# arduino_nano.net
KiCad netlist of a schematic drawn in EAGLE
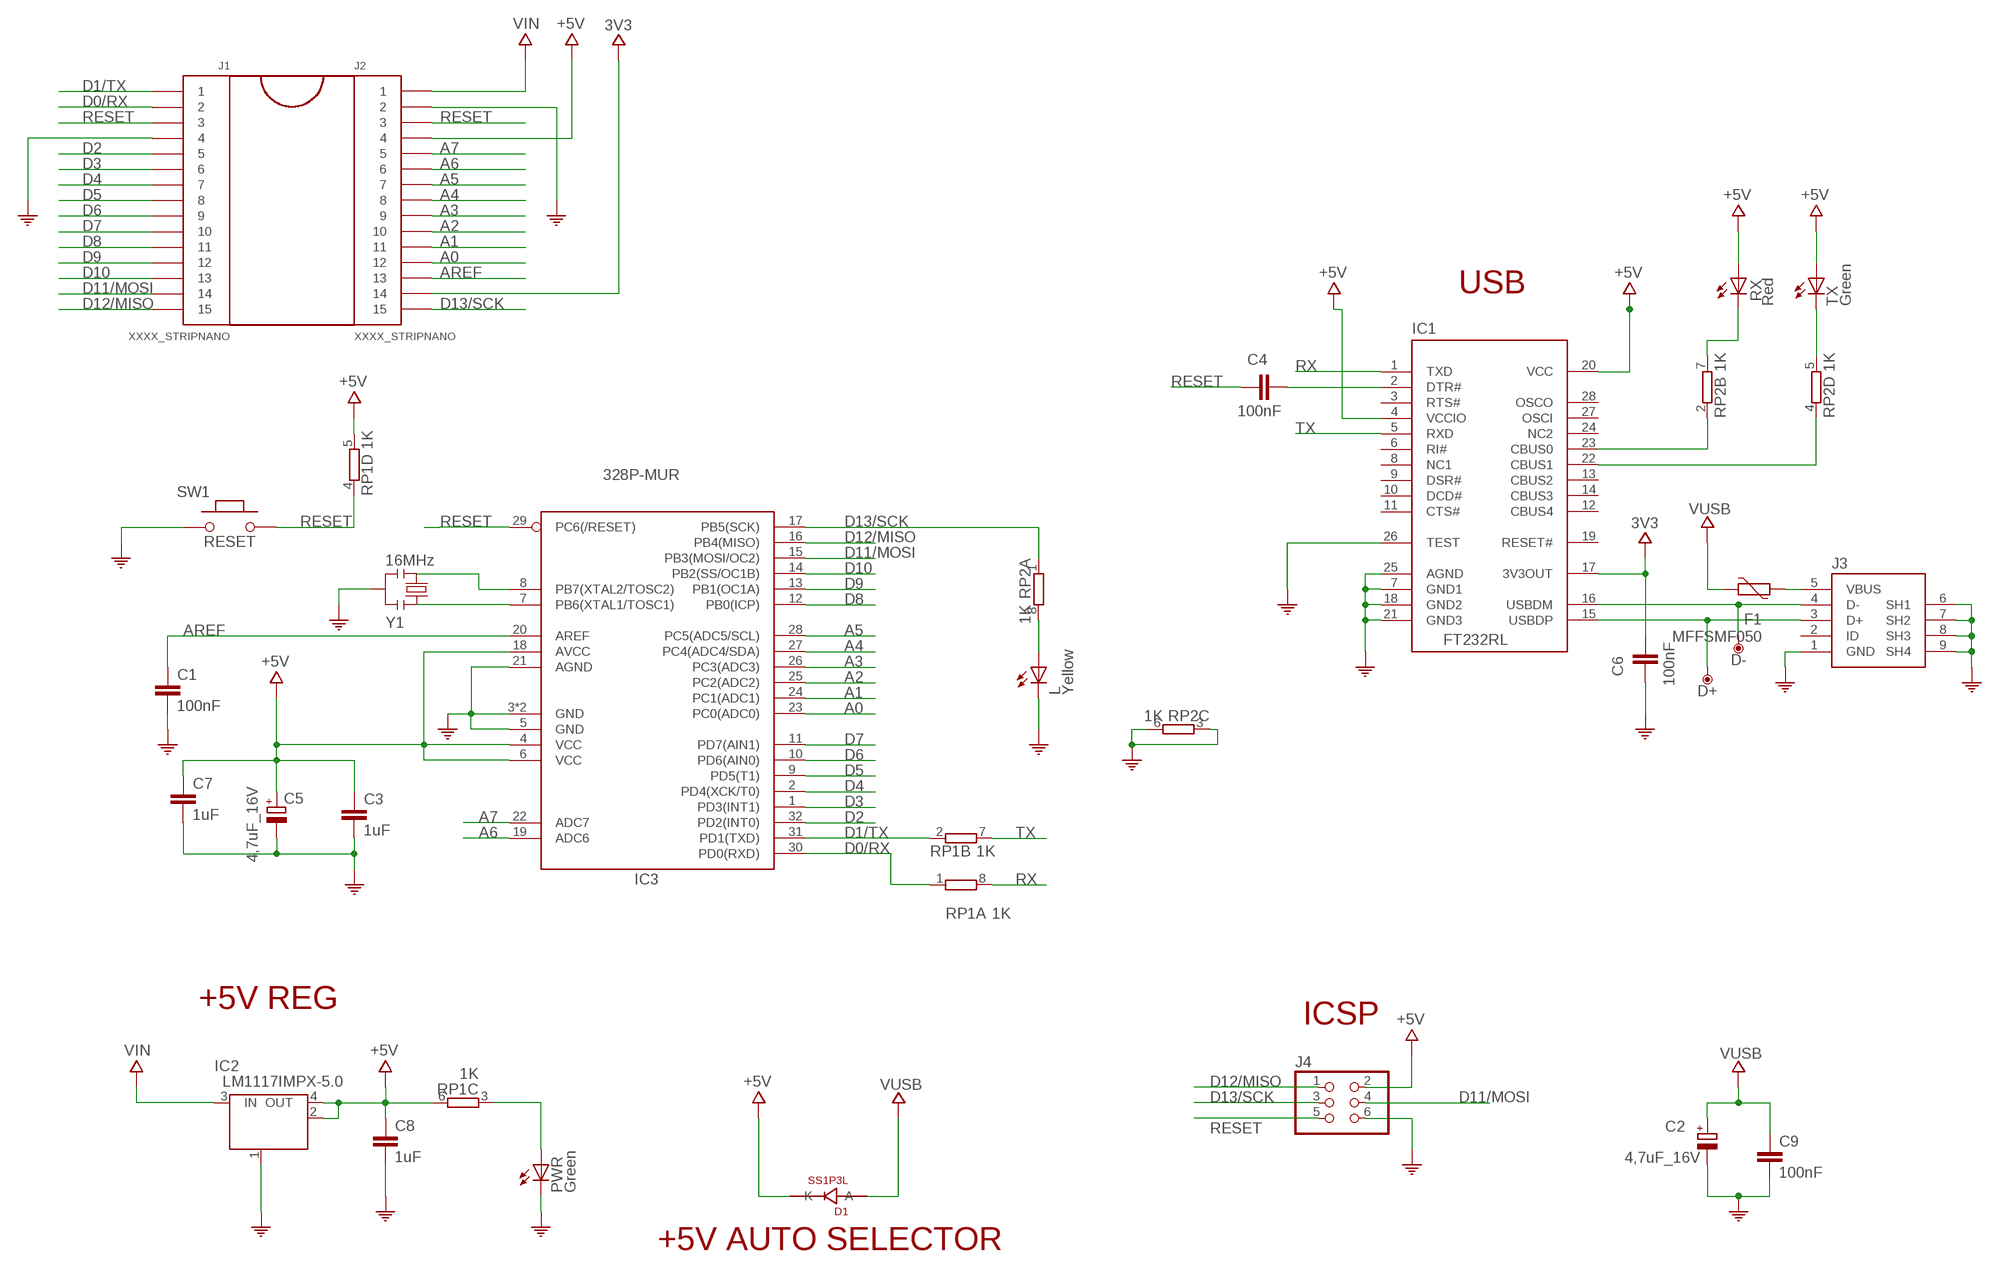
[diagram p0: schematic, sheet 1]

(export (version "E")
  (design (tool "Eeschema 10.0.6"))
  (components
    (comp (ref "C1")
      (value "100nF")
      (footprint "eagle-import:C0603-ROUND")
      (fields (field (name "PART_NUMBER") "cl10b104kbnc"))
      (libsource (lib "eagle-import") (part "0015_100NF_0603"))
    )
    (comp (ref "C2")
      (value "4,7uF_16V")
      (footprint "eagle-import:TAN-A")
      (fields (field (name "PART_NUMBER") "TAJA475MO16RNJ"))
      (libsource (lib "eagle-import") (part "0833_TAJA475MO16RNJ"))
    )
    (comp (ref "C3")
      (value "1uF")
      (footprint "eagle-import:C0603-ROUND")
      (fields (field (name "PART_NUMBER") "1uF_0603/GRM188R61E105KA12D"))
      (libsource (lib "eagle-import") (part "0006_1UF_0603/GRM188R61E105KA12D"))
    )
    (comp (ref "C4")
      (value "100nF")
      (footprint "eagle-import:C0603-ROUND")
      (fields (field (name "PART_NUMBER") "cl10b104kbnc"))
      (libsource (lib "eagle-import") (part "0015_100NF_0603"))
    )
    (comp (ref "C5")
      (value "4,7uF_16V")
      (footprint "eagle-import:TAN-A")
      (fields (field (name "PART_NUMBER") "TAJA475MO16RNJ"))
      (libsource (lib "eagle-import") (part "0833_TAJA475MO16RNJ"))
    )
    (comp (ref "C6")
      (value "100nF")
      (footprint "eagle-import:C0603-ROUND")
      (fields (field (name "PART_NUMBER") "cl10b104kbnc"))
      (libsource (lib "eagle-import") (part "0015_100NF_0603"))
    )
    (comp (ref "C7")
      (value "1uF")
      (footprint "eagle-import:C0603-ROUND")
      (fields (field (name "PART_NUMBER") "1uF_0603/GRM188R61E105KA12D"))
      (libsource (lib "eagle-import") (part "0006_1UF_0603/GRM188R61E105KA12D"))
    )
    (comp (ref "C8")
      (value "1uF")
      (footprint "eagle-import:C0603-ROUND")
      (fields (field (name "PART_NUMBER") "1uF_0603/GRM188R61E105KA12D"))
      (libsource (lib "eagle-import") (part "0006_1UF_0603/GRM188R61E105KA12D"))
    )
    (comp (ref "C9")
      (value "100nF")
      (footprint "eagle-import:C0603-ROUND")
      (fields (field (name "PART_NUMBER") "cl10b104kbnc"))
      (libsource (lib "eagle-import") (part "0015_100NF_0603"))
    )
    (comp (ref "D+")
      (value "DNP")
      (footprint "eagle-import:TP-1.00MM")
      (libsource (lib "eagle-import") (part "TPTP-1.00MM"))
    )
    (comp (ref "D-")
      (value "DNP")
      (footprint "eagle-import:TP-1.00MM")
      (libsource (lib "eagle-import") (part "TPTP-1.00MM"))
    )
    (comp (ref "D1")
      (value "SS1P3L")
      (footprint "eagle-import:DO220AAL")
      (fields (field (name "PART_NUMBER") "SS1P3L-M3/84A"))
      (libsource (lib "eagle-import") (part "0025_SS1P3L-M3/84A"))
    )
    (comp (ref "F1")
      (value "MFFSMF050")
      (footprint "eagle-import:0603-1608X90N")
      (fields (field (name "MANUFACTURER") "Bourns Inc "))
      (libsource (lib "eagle-import") (part "PTC"))
    )
    (comp (ref "IC1")
      (value "FT232RL")
      (footprint "eagle-import:SSOP28")
      (libsource (lib "eagle-import") (part "0226_FT232RL"))
    )
    (comp (ref "IC2")
      (value "LM1117IMPX-5.0")
      (footprint "eagle-import:LINEAR_SOT223")
      (libsource (lib "eagle-import") (part "0022_LM1117IMPX-5.0"))
    )
    (comp (ref "IC3")
      (value "328P-MUR")
      (footprint "eagle-import:VQFN32")
      (fields (field (name "MANUFACTURER") "ATMEL"))
      (libsource (lib "eagle-import") (part "ATMEGA328P-32MUR"))
    )
    (comp (ref "J1")
      (value "XXXX_STRIPNANO")
      (footprint "eagle-import:HEAD15-NOSS")
      (libsource (lib "eagle-import") (part "XXXX_STRIPNANO"))
    )
    (comp (ref "J2")
      (value "XXXX_STRIPNANO")
      (footprint "eagle-import:HEAD15-NOSS")
      (libsource (lib "eagle-import") (part "XXXX_STRIPNANO"))
    )
    (comp (ref "J3")
      (value "0219_14850")
      (footprint "eagle-import:USB-MINI-B_2")
      (fields (field (name "PART_NUMBER") "14850"))
      (libsource (lib "eagle-import") (part "0219_14850"))
    )
    (comp (ref "J4")
      (value "0114_PH254-203DF118A00V")
      (footprint "eagle-import:2X03")
      (fields (field (name "PART_NUMBER") "PH254-203DF118A00V"))
      (libsource (lib "eagle-import") (part "0114_PH254-203DF118A00V"))
    )
    (comp (ref "L")
      (value "Yellow")
      (footprint "eagle-import:CHIPLED_0805")
      (fields (field (name "PART_NUMBER") "KPT-2012YC"))
      (libsource (lib "eagle-import") (part "0044_KPT-2012YC"))
    )
    (comp (ref "PWR")
      (value "Green")
      (footprint "eagle-import:CHIPLED_0805")
      (fields (field (name "PART_NUMBER") "KPT-2012SGC"))
      (libsource (lib "eagle-import") (part "0043_KPT-2012SGC"))
    )
    (comp (ref "RP1")
      (value "1K")
      (footprint "eagle-import:CAY16")
      (fields (field (name "PART_NUMBER") "064R_1K_/_CAY16-102J4LF"))
      (libsource (lib "eagle-import") (part "0005_064R_1K_/_CAY16-102J4LF"))
    )
    (comp (ref "RP2")
      (value "1K")
      (footprint "eagle-import:CAY16")
      (fields (field (name "PART_NUMBER") "064R_1K_/_CAY16-102J4LF"))
      (libsource (lib "eagle-import") (part "0005_064R_1K_/_CAY16-102J4LF"))
    )
    (comp (ref "RX")
      (value "Red")
      (footprint "eagle-import:CHIPLED_0805")
      (fields (field (name "PART_NUMBER") "KTP-2012SURCK"))
      (libsource (lib "eagle-import") (part "0181_KTP-2012SURCK"))
    )
    (comp (ref "SW1")
      (value "RESET")
      (footprint "eagle-import:SMD_157SW")
      (fields (field (name "PART_NUMBER") "IT-1185AP1C-160G-G_T&R"))
      (libsource (lib "eagle-import") (part "0173_IT-1185AP1C-160G-G_T&R"))
    )
    (comp (ref "TX")
      (value "Green")
      (footprint "eagle-import:CHIPLED_0805")
      (fields (field (name "PART_NUMBER") "KPT-2012SGC"))
      (libsource (lib "eagle-import") (part "0043_KPT-2012SGC"))
    )
    (comp (ref "Y1")
      (value "16MHz")
      (footprint "eagle-import:RESONATOR")
      (fields (field (name "PART_NUMBER") "CSTCE16M0V53-R0"))
      (libsource (lib "eagle-import") (part "0011_CSTCE16M0V53-R0"))
    )
  )
  (nets
    (net (code "1") (name "+5V") (class "Default")
      (node (ref "C3") (pin "1") (pinfunction "1_1") (pintype "passive"))
      (node (ref "C5") (pin "1") (pinfunction "+_1") (pintype "passive"))
      (node (ref "C7") (pin "1") (pinfunction "1_1") (pintype "passive"))
      (node (ref "C8") (pin "1") (pinfunction "1_1") (pintype "passive"))
      (node (ref "D1") (pin "P$1") (pinfunction "K_P$1") (pintype "bidirectional"))
      (node (ref "IC1") (pin "20") (pinfunction "VCC_20") (pintype "power_in"))
      (node (ref "IC1") (pin "4") (pinfunction "VCCIO_4") (pintype "power_in"))
      (node (ref "IC2") (pin "2") (pinfunction "OUT_2") (pintype "passive"))
      (node (ref "IC2") (pin "4") (pinfunction "OUT_4") (pintype "passive"))
      (node (ref "IC3") (pin "18") (pinfunction "AVCC_18") (pintype "bidirectional"))
      (node (ref "IC3") (pin "4") (pinfunction "VCC_4") (pintype "bidirectional"))
      (node (ref "IC3") (pin "6") (pinfunction "VCC_6") (pintype "bidirectional"))
      (node (ref "J2") (pin "4") (pinfunction "4_4") (pintype "passive"))
      (node (ref "J4") (pin "2") (pinfunction "2_2") (pintype "passive"))
      (node (ref "RP1") (pin "5") (pinfunction "2_5") (pintype "passive"))
      (node (ref "RP1") (pin "6") (pinfunction "2_6") (pintype "passive"))
      (node (ref "RX") (pin "A") (pinfunction "A_A") (pintype "passive"))
      (node (ref "TX") (pin "A") (pinfunction "A_A") (pintype "passive"))
    )
    (net (code "2") (name "/A0") (class "Default")
      (node (ref "IC3") (pin "23") (pinfunction "PC0(ADC0)_23") (pintype "bidirectional"))
      (node (ref "J2") (pin "12") (pinfunction "12_12") (pintype "passive"))
    )
    (net (code "3") (name "/A1") (class "Default")
      (node (ref "IC3") (pin "24") (pinfunction "PC1(ADC1)_24") (pintype "bidirectional"))
      (node (ref "J2") (pin "11") (pinfunction "11_11") (pintype "passive"))
    )
    (net (code "4") (name "/A2") (class "Default")
      (node (ref "IC3") (pin "25") (pinfunction "PC2(ADC2)_25") (pintype "bidirectional"))
      (node (ref "J2") (pin "10") (pinfunction "10_10") (pintype "passive"))
    )
    (net (code "5") (name "/A3") (class "Default")
      (node (ref "IC3") (pin "26") (pinfunction "PC3(ADC3)_26") (pintype "bidirectional"))
      (node (ref "J2") (pin "9") (pinfunction "9_9") (pintype "passive"))
    )
    (net (code "6") (name "/A4") (class "Default")
      (node (ref "IC3") (pin "27") (pinfunction "PC4(ADC4/SDA)_27") (pintype "bidirectional"))
      (node (ref "J2") (pin "8") (pinfunction "8_8") (pintype "passive"))
    )
    (net (code "7") (name "/A5") (class "Default")
      (node (ref "IC3") (pin "28") (pinfunction "PC5(ADC5/SCL)_28") (pintype "bidirectional"))
      (node (ref "J2") (pin "7") (pinfunction "7_7") (pintype "passive"))
    )
    (net (code "8") (name "/A6") (class "Default")
      (node (ref "IC3") (pin "19") (pinfunction "ADC6_19") (pintype "bidirectional"))
      (node (ref "J2") (pin "6") (pinfunction "6_6") (pintype "passive"))
    )
    (net (code "9") (name "/A7") (class "Default")
      (node (ref "IC3") (pin "22") (pinfunction "ADC7_22") (pintype "bidirectional"))
      (node (ref "J2") (pin "5") (pinfunction "5_5") (pintype "passive"))
    )
    (net (code "10") (name "/AREF") (class "Default")
      (node (ref "C1") (pin "1") (pinfunction "1_1") (pintype "passive"))
      (node (ref "IC3") (pin "20") (pinfunction "AREF_20") (pintype "bidirectional"))
      (node (ref "J2") (pin "13") (pinfunction "13_13") (pintype "passive"))
    )
    (net (code "11") (name "/D0{slash}RX") (class "Default")
      (node (ref "IC3") (pin "30") (pinfunction "PD0(RXD)_30") (pintype "bidirectional"))
      (node (ref "J1") (pin "2") (pinfunction "2_2") (pintype "passive"))
      (node (ref "RP1") (pin "1") (pinfunction "1_1") (pintype "passive"))
    )
    (net (code "12") (name "/D1{slash}TX") (class "Default")
      (node (ref "IC3") (pin "31") (pinfunction "PD1(TXD)_31") (pintype "bidirectional"))
      (node (ref "J1") (pin "1") (pinfunction "1_1") (pintype "passive"))
      (node (ref "RP1") (pin "2") (pinfunction "1_2") (pintype "passive"))
    )
    (net (code "13") (name "/D2") (class "Default")
      (node (ref "IC3") (pin "32") (pinfunction "PD2(INT0)_32") (pintype "bidirectional"))
      (node (ref "J1") (pin "5") (pinfunction "5_5") (pintype "passive"))
    )
    (net (code "14") (name "/D3") (class "Default")
      (node (ref "IC3") (pin "1") (pinfunction "PD3(INT1)_1") (pintype "bidirectional"))
      (node (ref "J1") (pin "6") (pinfunction "6_6") (pintype "passive"))
    )
    (net (code "15") (name "/D4") (class "Default")
      (node (ref "IC3") (pin "2") (pinfunction "PD4(XCK/T0)_2") (pintype "bidirectional"))
      (node (ref "J1") (pin "7") (pinfunction "7_7") (pintype "passive"))
    )
    (net (code "16") (name "/D5") (class "Default")
      (node (ref "IC3") (pin "9") (pinfunction "PD5(T1)_9") (pintype "bidirectional"))
      (node (ref "J1") (pin "8") (pinfunction "8_8") (pintype "passive"))
    )
    (net (code "17") (name "/D6") (class "Default")
      (node (ref "IC3") (pin "10") (pinfunction "PD6(AIN0)_10") (pintype "bidirectional"))
      (node (ref "J1") (pin "9") (pinfunction "9_9") (pintype "passive"))
    )
    (net (code "18") (name "/D7") (class "Default")
      (node (ref "IC3") (pin "11") (pinfunction "PD7(AIN1)_11") (pintype "bidirectional"))
      (node (ref "J1") (pin "10") (pinfunction "10_10") (pintype "passive"))
    )
    (net (code "19") (name "/D8") (class "Default")
      (node (ref "IC3") (pin "12") (pinfunction "PB0(ICP)_12") (pintype "bidirectional"))
      (node (ref "J1") (pin "11") (pinfunction "11_11") (pintype "passive"))
    )
    (net (code "20") (name "/D9") (class "Default")
      (node (ref "IC3") (pin "13") (pinfunction "PB1(OC1A)_13") (pintype "bidirectional"))
      (node (ref "J1") (pin "12") (pinfunction "12_12") (pintype "passive"))
    )
    (net (code "21") (name "/D10") (class "Default")
      (node (ref "IC3") (pin "14") (pinfunction "PB2(SS/OC1B)_14") (pintype "bidirectional"))
      (node (ref "J1") (pin "13") (pinfunction "13_13") (pintype "passive"))
    )
    (net (code "22") (name "/D11{slash}MOSI") (class "Default")
      (node (ref "IC3") (pin "15") (pinfunction "PB3(MOSI/OC2)_15") (pintype "bidirectional"))
      (node (ref "J1") (pin "14") (pinfunction "14_14") (pintype "passive"))
      (node (ref "J4") (pin "4") (pinfunction "4_4") (pintype "passive"))
    )
    (net (code "23") (name "/D12{slash}MISO") (class "Default")
      (node (ref "IC3") (pin "16") (pinfunction "PB4(MISO)_16") (pintype "bidirectional"))
      (node (ref "J1") (pin "15") (pinfunction "15_15") (pintype "passive"))
      (node (ref "J4") (pin "1") (pinfunction "1_1") (pintype "passive"))
    )
    (net (code "24") (name "/D13{slash}SCK") (class "Default")
      (node (ref "IC3") (pin "17") (pinfunction "PB5(SCK)_17") (pintype "bidirectional"))
      (node (ref "J2") (pin "15") (pinfunction "15_15") (pintype "passive"))
      (node (ref "J4") (pin "3") (pinfunction "3_3") (pintype "passive"))
      (node (ref "RP2") (pin "1") (pinfunction "1_1") (pintype "passive"))
    )
    (net (code "25") (name "/RESET") (class "Default")
      (node (ref "C4") (pin "1") (pinfunction "1_1") (pintype "passive"))
      (node (ref "IC3") (pin "29") (pinfunction "PC6(/RESET)_29") (pintype "bidirectional"))
      (node (ref "J1") (pin "3") (pinfunction "3_3") (pintype "passive"))
      (node (ref "J2") (pin "3") (pinfunction "3_3") (pintype "passive"))
      (node (ref "J4") (pin "5") (pinfunction "5_5") (pintype "passive"))
      (node (ref "RP1") (pin "4") (pinfunction "1_4") (pintype "passive"))
      (node (ref "SW1") (pin "2") (pinfunction "2_2") (pintype "passive"))
    )
    (net (code "26") (name "/RX") (class "Default")
      (node (ref "IC1") (pin "1") (pinfunction "TXD_1") (pintype "output"))
      (node (ref "RP1") (pin "8") (pinfunction "2_8") (pintype "passive"))
      (node (ref "RP2") (pin "7") (pinfunction "2_7") (pintype "passive"))
      (node (ref "RX") (pin "C") (pinfunction "C_C") (pintype "passive"))
    )
    (net (code "27") (name "/TX") (class "Default")
      (node (ref "IC1") (pin "5") (pinfunction "RXD_5") (pintype "input"))
      (node (ref "RP1") (pin "7") (pinfunction "2_7") (pintype "passive"))
    )
    (net (code "28") (name "3V3") (class "Default")
      (node (ref "C6") (pin "2") (pinfunction "2_2") (pintype "passive"))
      (node (ref "IC1") (pin "17") (pinfunction "3V3OUT_17") (pintype "power_in"))
      (node (ref "J2") (pin "14") (pinfunction "14_14") (pintype "passive"))
    )
    (net (code "29") (name "COM") (class "Default")
      (node (ref "C1") (pin "2") (pinfunction "2_2") (pintype "passive"))
      (node (ref "C2") (pin "2") (pinfunction "-_2") (pintype "passive"))
      (node (ref "C3") (pin "2") (pinfunction "2_2") (pintype "passive"))
      (node (ref "C5") (pin "2") (pinfunction "-_2") (pintype "passive"))
      (node (ref "C6") (pin "1") (pinfunction "1_1") (pintype "passive"))
      (node (ref "C7") (pin "2") (pinfunction "2_2") (pintype "passive"))
      (node (ref "C8") (pin "2") (pinfunction "2_2") (pintype "passive"))
      (node (ref "C9") (pin "2") (pinfunction "2_2") (pintype "passive"))
      (node (ref "IC1") (pin "18") (pinfunction "GND2_18") (pintype "power_in"))
      (node (ref "IC1") (pin "21") (pinfunction "GND3_21") (pintype "power_in"))
      (node (ref "IC1") (pin "25") (pinfunction "AGND_25") (pintype "power_in"))
      (node (ref "IC1") (pin "26") (pinfunction "TEST_26") (pintype "bidirectional"))
      (node (ref "IC1") (pin "7") (pinfunction "GND1_7") (pintype "power_in"))
      (node (ref "IC2") (pin "1") (pinfunction "GND/ADJ_1") (pintype "input"))
      (node (ref "IC3") (pin "21") (pinfunction "AGND_21") (pintype "bidirectional"))
      (node (ref "IC3") (pin "3") (pinfunction "GND_3") (pintype "bidirectional"))
      (node (ref "IC3") (pin "33") (pinfunction "GND_33") (pintype "bidirectional"))
      (node (ref "IC3") (pin "5") (pinfunction "GND_5") (pintype "bidirectional"))
      (node (ref "J1") (pin "4") (pinfunction "4_4") (pintype "passive"))
      (node (ref "J2") (pin "2") (pinfunction "2_2") (pintype "passive"))
      (node (ref "J3") (pin "1") (pinfunction "GND_1") (pintype "passive"))
      (node (ref "J3") (pin "6") (pinfunction "SH1_6") (pintype "passive"))
      (node (ref "J3") (pin "7") (pinfunction "SH2_7") (pintype "passive"))
      (node (ref "J3") (pin "8") (pinfunction "SH3_8") (pintype "passive"))
      (node (ref "J3") (pin "9") (pinfunction "SH4_9") (pintype "passive"))
      (node (ref "J4") (pin "6") (pinfunction "6_6") (pintype "passive"))
      (node (ref "L") (pin "C") (pinfunction "C_C") (pintype "passive"))
      (node (ref "PWR") (pin "C") (pinfunction "C_C") (pintype "passive"))
      (node (ref "RP2") (pin "3") (pinfunction "1_3") (pintype "passive"))
      (node (ref "RP2") (pin "6") (pinfunction "2_6") (pintype "passive"))
      (node (ref "SW1") (pin "1") (pinfunction "1_1") (pintype "passive"))
      (node (ref "Y1") (pin "2") (pinfunction "2_2") (pintype "passive"))
    )
    (net (code "30") (name "Net-(D+-P$1)") (class "Default")
      (node (ref "D+") (pin "X") (pinfunction "P$1_X") (pintype "passive"))
      (node (ref "IC1") (pin "15") (pinfunction "USBDP_15") (pintype "bidirectional"))
      (node (ref "J3") (pin "3") (pinfunction "D+_3") (pintype "bidirectional"))
    )
    (net (code "31") (name "Net-(D--P$1)") (class "Default")
      (node (ref "D-") (pin "X") (pinfunction "P$1_X") (pintype "passive"))
      (node (ref "IC1") (pin "16") (pinfunction "USBDM_16") (pintype "bidirectional"))
      (node (ref "J3") (pin "4") (pinfunction "D-_4") (pintype "bidirectional"))
    )
    (net (code "32") (name "Net-(IC1-CBUS0)") (class "Default")
      (node (ref "IC1") (pin "23") (pinfunction "CBUS0_23") (pintype "bidirectional"))
      (node (ref "RP2") (pin "2") (pinfunction "1_2") (pintype "passive"))
    )
    (net (code "33") (name "Net-(IC1-CBUS1)") (class "Default")
      (node (ref "IC1") (pin "22") (pinfunction "CBUS1_22") (pintype "bidirectional"))
      (node (ref "RP2") (pin "4") (pinfunction "1_4") (pintype "passive"))
    )
    (net (code "34") (name "Net-(IC1-DTR#)") (class "Default")
      (node (ref "C4") (pin "2") (pinfunction "2_2") (pintype "passive"))
      (node (ref "IC1") (pin "2") (pinfunction "DTR#_2") (pintype "output"))
    )
    (net (code "35") (name "Net-(IC3-PB6(XTAL1{slash}TOSC1))") (class "Default")
      (node (ref "IC3") (pin "7") (pinfunction "PB6(XTAL1/TOSC1)_7") (pintype "bidirectional"))
      (node (ref "Y1") (pin "1") (pinfunction "1_1") (pintype "passive"))
    )
    (net (code "36") (name "Net-(IC3-PB7(XTAL2{slash}TOSC2))") (class "Default")
      (node (ref "IC3") (pin "8") (pinfunction "PB7(XTAL2/TOSC2)_8") (pintype "bidirectional"))
      (node (ref "Y1") (pin "3") (pinfunction "3_3") (pintype "passive"))
    )
    (net (code "37") (name "Net-(J3-VBUS)") (class "Default")
      (node (ref "F1") (pin "2") (pinfunction "2_2") (pintype "passive"))
      (node (ref "J3") (pin "5") (pinfunction "VBUS_5") (pintype "power_in"))
    )
    (net (code "38") (name "Net-(RP1C-1)") (class "Default")
      (node (ref "PWR") (pin "A") (pinfunction "A_A") (pintype "passive"))
      (node (ref "RP1") (pin "3") (pinfunction "1_3") (pintype "passive"))
    )
    (net (code "39") (name "Net-(RP2A-2)") (class "Default")
      (node (ref "L") (pin "A") (pinfunction "A_A") (pintype "passive"))
      (node (ref "RP2") (pin "8") (pinfunction "2_8") (pintype "passive"))
    )
    (net (code "40") (name "Net-(RP2D-2)") (class "Default")
      (node (ref "RP2") (pin "5") (pinfunction "2_5") (pintype "passive"))
      (node (ref "TX") (pin "C") (pinfunction "C_C") (pintype "passive"))
    )
    (net (code "41") (name "VIN") (class "Default")
      (node (ref "IC2") (pin "3") (pinfunction "IN_3") (pintype "input"))
      (node (ref "J2") (pin "1") (pinfunction "1_1") (pintype "passive"))
    )
    (net (code "42") (name "VUSB") (class "Default")
      (node (ref "C2") (pin "1") (pinfunction "+_1") (pintype "passive"))
      (node (ref "C9") (pin "1") (pinfunction "1_1") (pintype "passive"))
      (node (ref "D1") (pin "P$2") (pinfunction "A_P$2") (pintype "bidirectional"))
      (node (ref "F1") (pin "1") (pinfunction "1_1") (pintype "passive"))
    )
    (net (code "43") (name "unconnected-(IC1-CBUS2-Pad13)") (class "Default")
      (node (ref "IC1") (pin "13") (pinfunction "CBUS2_13") (pintype "bidirectional"))
    )
    (net (code "44") (name "unconnected-(IC1-CBUS3-Pad14)") (class "Default")
      (node (ref "IC1") (pin "14") (pinfunction "CBUS3_14") (pintype "bidirectional"))
    )
    (net (code "45") (name "unconnected-(IC1-CBUS4-Pad12)") (class "Default")
      (node (ref "IC1") (pin "12") (pinfunction "CBUS4_12") (pintype "bidirectional"))
    )
    (net (code "46") (name "unconnected-(IC1-CTS#-Pad11)") (class "Default")
      (node (ref "IC1") (pin "11") (pinfunction "CTS#_11") (pintype "bidirectional"))
    )
    (net (code "47") (name "unconnected-(IC1-DCD#-Pad10)") (class "Default")
      (node (ref "IC1") (pin "10") (pinfunction "DCD#_10") (pintype "bidirectional"))
    )
    (net (code "48") (name "unconnected-(IC1-DSR#-Pad9)") (class "Default")
      (node (ref "IC1") (pin "9") (pinfunction "DSR#_9") (pintype "bidirectional"))
    )
    (net (code "49") (name "unconnected-(IC1-NC1-Pad8)") (class "Default")
      (node (ref "IC1") (pin "8") (pinfunction "NC1_8") (pintype "bidirectional"))
    )
    (net (code "50") (name "unconnected-(IC1-NC2-Pad24)") (class "Default")
      (node (ref "IC1") (pin "24") (pinfunction "NC2_24") (pintype "no_connect"))
    )
    (net (code "51") (name "unconnected-(IC1-OSCI-Pad27)") (class "Default")
      (node (ref "IC1") (pin "27") (pinfunction "OSCI_27") (pintype "bidirectional"))
    )
    (net (code "52") (name "unconnected-(IC1-OSCO-Pad28)") (class "Default")
      (node (ref "IC1") (pin "28") (pinfunction "OSCO_28") (pintype "output"))
    )
    (net (code "53") (name "unconnected-(IC1-RESET#-Pad19)") (class "Default")
      (node (ref "IC1") (pin "19") (pinfunction "RESET#_19") (pintype "bidirectional"))
    )
    (net (code "54") (name "unconnected-(IC1-RI#-Pad6)") (class "Default")
      (node (ref "IC1") (pin "6") (pinfunction "RI#_6") (pintype "bidirectional"))
    )
    (net (code "55") (name "unconnected-(IC1-RTS#-Pad3)") (class "Default")
      (node (ref "IC1") (pin "3") (pinfunction "RTS#_3") (pintype "output"))
    )
    (net (code "56") (name "unconnected-(J3-ID-Pad2)") (class "Default")
      (node (ref "J3") (pin "2") (pinfunction "ID_2") (pintype "bidirectional"))
    )
  )
)
